# VIC-20_AV-Adaptor.net
KiCad netlist of a schematic drawn in EAGLE
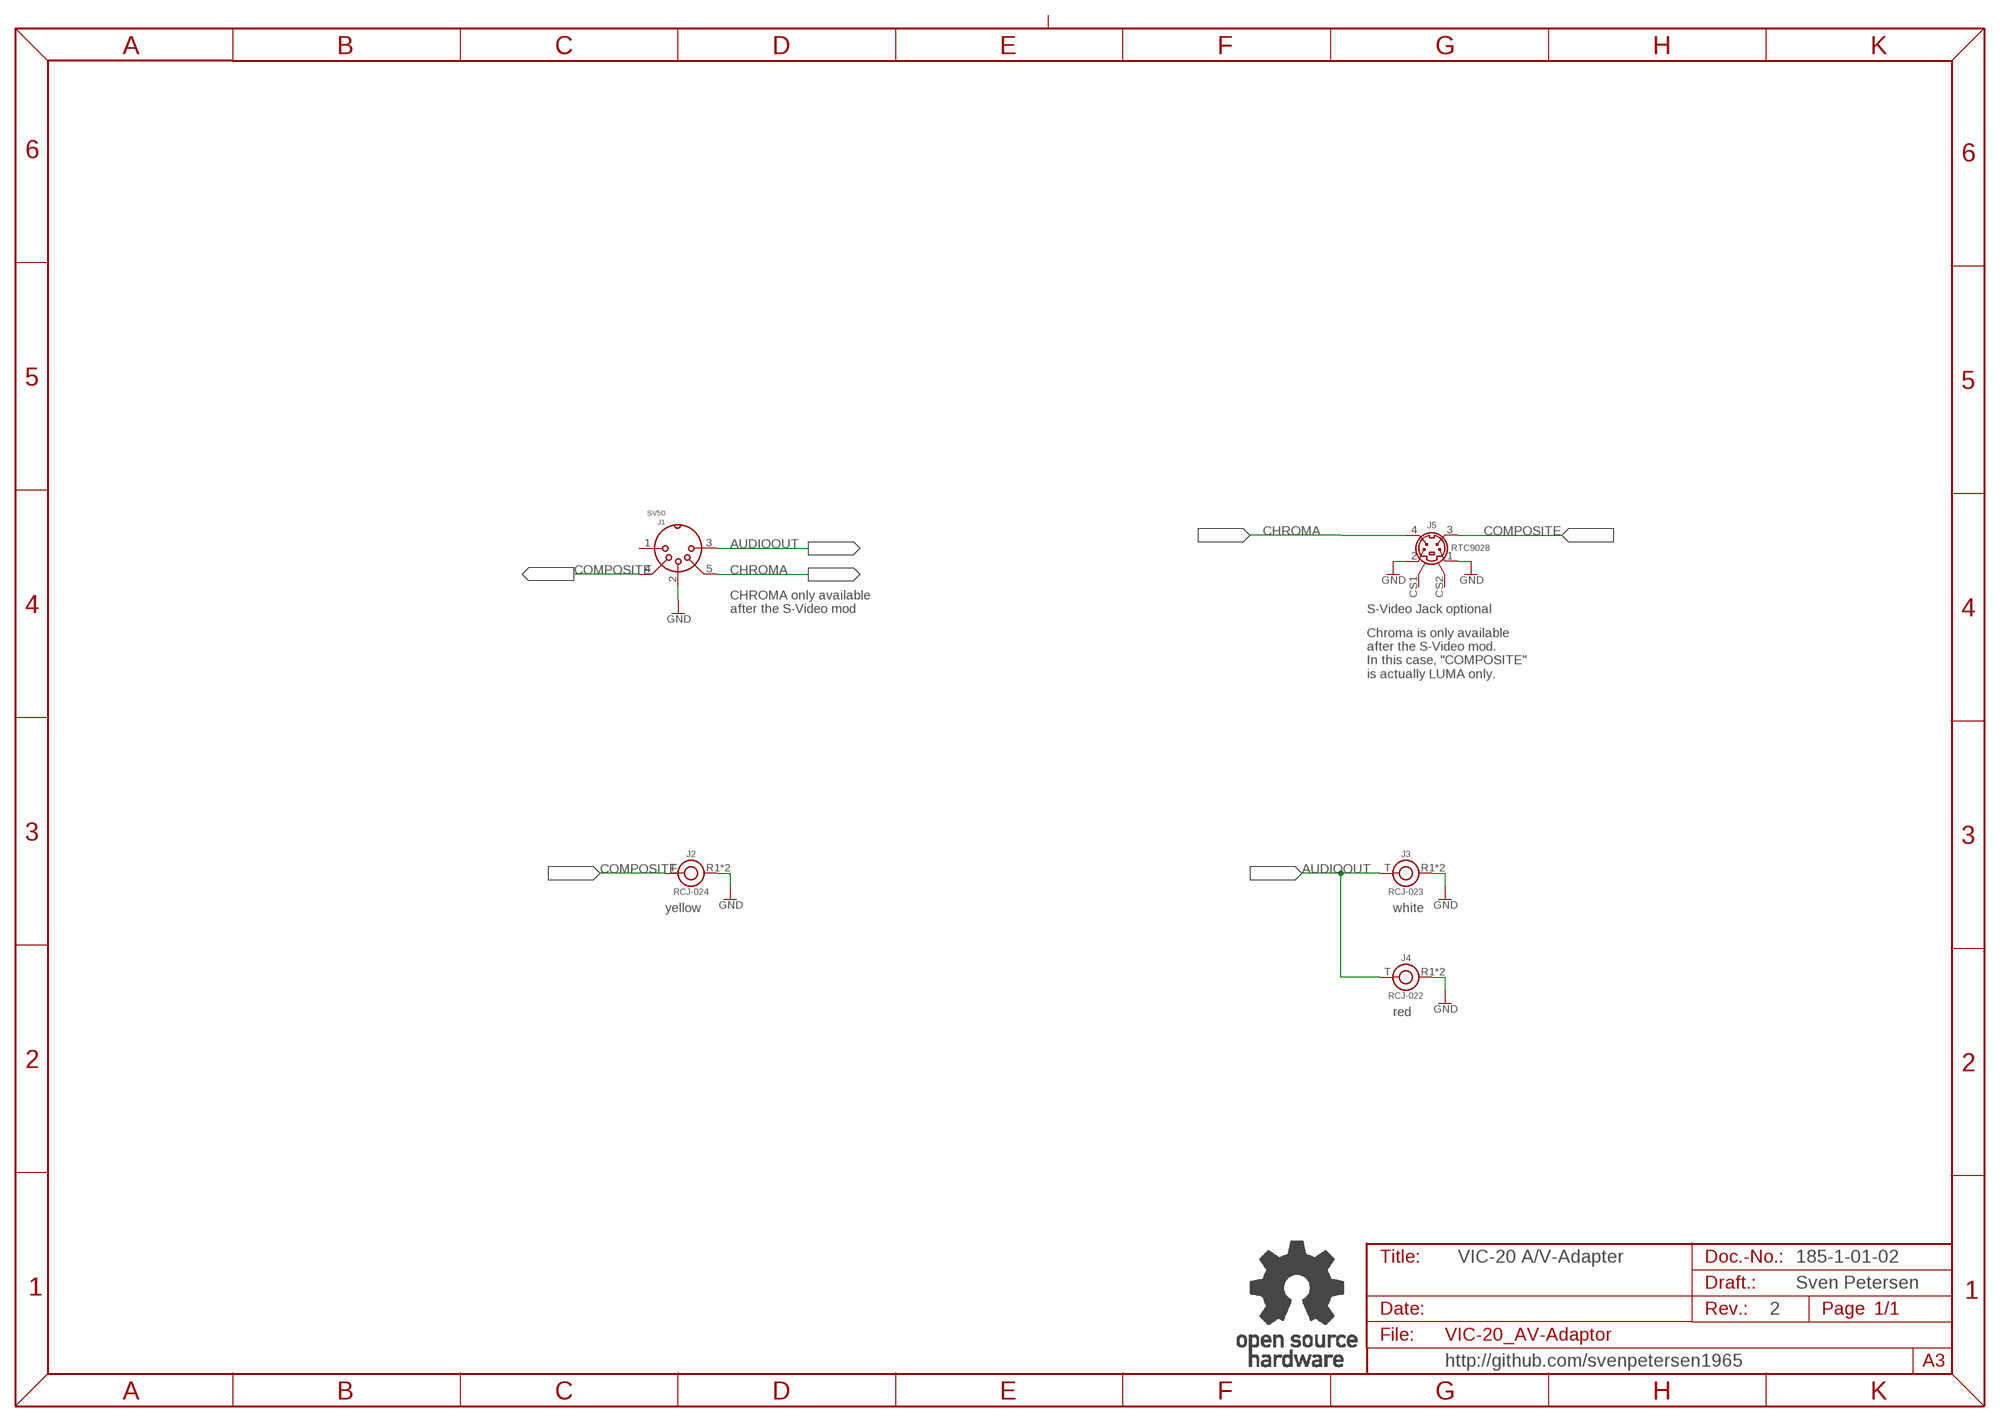
[diagram p0: schematic, sheet 1]

(export (version "E")
  (design (tool "Eeschema 10.0.6"))
  (components
    (comp (ref "J1")
      (value "SV50")
      (footprint "eagle-import:SV50_INNER")
      (libsource (lib "eagle-import") (part "SV50"))
    )
    (comp (ref "J2")
      (value "RCJ-024")
      (footprint "eagle-import:RCJ-02X")
      (libsource (lib "eagle-import") (part "RCJ-02X"))
    )
    (comp (ref "J3")
      (value "RCJ-023")
      (footprint "eagle-import:RCJ-02X")
      (libsource (lib "eagle-import") (part "RCJ-02X"))
    )
    (comp (ref "J4")
      (value "RCJ-022")
      (footprint "eagle-import:RCJ-02X")
      (libsource (lib "eagle-import") (part "RCJ-02X"))
    )
    (comp (ref "J5")
      (value "RTC9028")
      (footprint "eagle-import:MINIDIN4_V")
      (libsource (lib "eagle-import") (part "RTC9028"))
    )
    (comp (ref "U$25")
      (value "OPEN_SOURCE_HW")
      (footprint "eagle-import:OPENHW")
      (libsource (lib "eagle-import") (part "OPEN_SOURCE_HW"))
    )
  )
  (nets
    (net (code "1") (name "/AUDIOOUT") (class "Default")
      (node (ref "J1") (pin "3") (pinfunction "3_3") (pintype "bidirectional"))
      (node (ref "J3") (pin "T") (pinfunction "T_T") (pintype "bidirectional"))
      (node (ref "J4") (pin "T") (pinfunction "T_T") (pintype "bidirectional"))
    )
    (net (code "2") (name "/CHROMA") (class "Default")
      (node (ref "J1") (pin "5") (pinfunction "5_5") (pintype "bidirectional"))
      (node (ref "J5") (pin "4") (pinfunction "4_4") (pintype "bidirectional"))
    )
    (net (code "3") (name "/COMPOSITE") (class "Default")
      (node (ref "J1") (pin "4") (pinfunction "4_4") (pintype "bidirectional"))
      (node (ref "J2") (pin "T") (pinfunction "T_T") (pintype "bidirectional"))
      (node (ref "J5") (pin "3") (pinfunction "3_3") (pintype "bidirectional"))
    )
    (net (code "4") (name "GND") (class "Default")
      (node (ref "J1") (pin "2") (pinfunction "2_2") (pintype "bidirectional"))
      (node (ref "J2") (pin "R1") (pinfunction "R_R1") (pintype "bidirectional"))
      (node (ref "J2") (pin "R2") (pinfunction "R_R2") (pintype "bidirectional"))
      (node (ref "J3") (pin "R1") (pinfunction "R_R1") (pintype "bidirectional"))
      (node (ref "J3") (pin "R2") (pinfunction "R_R2") (pintype "bidirectional"))
      (node (ref "J4") (pin "R1") (pinfunction "R_R1") (pintype "bidirectional"))
      (node (ref "J4") (pin "R2") (pinfunction "R_R2") (pintype "bidirectional"))
      (node (ref "J5") (pin "1") (pinfunction "1_1") (pintype "bidirectional"))
      (node (ref "J5") (pin "2") (pinfunction "2_2") (pintype "bidirectional"))
    )
    (net (code "5") (name "unconnected-(J1-Pad1)") (class "Default")
      (node (ref "J1") (pin "1") (pinfunction "1_1") (pintype "bidirectional"))
    )
    (net (code "6") (name "unconnected-(J5-PadCS1)") (class "Default")
      (node (ref "J5") (pin "CS1") (pinfunction "CS1_CS1") (pintype "bidirectional"))
    )
    (net (code "7") (name "unconnected-(J5-PadCS2)") (class "Default")
      (node (ref "J5") (pin "CS2") (pinfunction "CS2_CS2") (pintype "bidirectional"))
    )
  )
)
